# design.net
KiCad netlist of a schematic drawn in Altium Designer
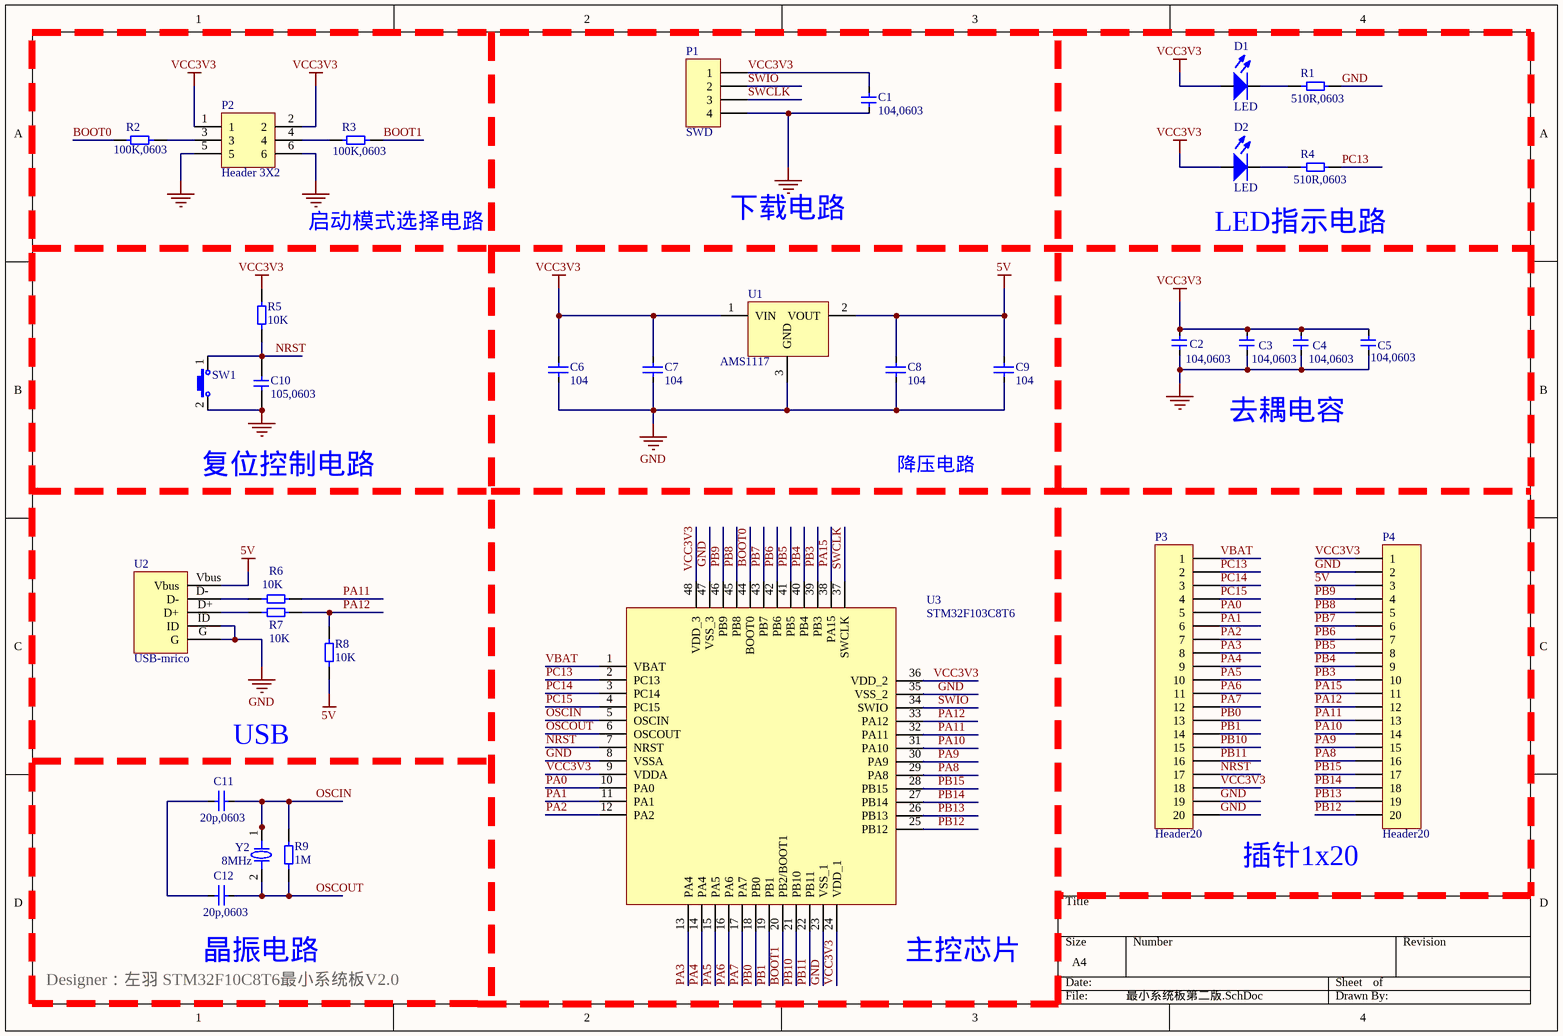
[diagram p0: 最小系统板第二版.SchDoc]

(export (version "E")
  (design (tool "Eeschema 10.0.6"))
  (components
    (comp (ref "C1")
      (value "104,0603")
      (footprint "0603C")
      (description "电容")
      (libsource (lib "原理图库") (part "CAP"))
    )
    (comp (ref "C2")
      (value "104,0603")
      (footprint "0603C")
      (description "电容")
      (libsource (lib "原理图库") (part "CAP"))
    )
    (comp (ref "C3")
      (value "104,0603")
      (footprint "0603C")
      (description "电容")
      (libsource (lib "原理图库") (part "CAP"))
    )
    (comp (ref "C4")
      (value "104,0603")
      (footprint "0603C")
      (description "电容")
      (libsource (lib "原理图库") (part "CAP"))
    )
    (comp (ref "C5")
      (value "104,0603")
      (footprint "0603C")
      (description "电容")
      (libsource (lib "原理图库") (part "CAP"))
    )
    (comp (ref "C6") (value "104") (footprint "0603C") (description "电容") (libsource (lib "") (part "CAP_2")))
    (comp (ref "C7") (value "104") (footprint "0603C") (description "电容") (libsource (lib "") (part "CAP_1")))
    (comp (ref "C8") (value "104") (footprint "0603C") (description "电容") (libsource (lib "") (part "CAP_1")))
    (comp (ref "C9") (value "104") (footprint "0603C") (description "电容") (libsource (lib "") (part "CAP_1")))
    (comp (ref "C10")
      (value "105,0603")
      (footprint "0603C")
      (description "电容")
      (libsource (lib "") (part "CAP_3"))
    )
    (comp (ref "C11")
      (value "20p,0603")
      (footprint "0603C")
      (description "电容")
      (libsource (lib "") (part "CAP_1"))
    )
    (comp (ref "C12")
      (value "20p,0603")
      (footprint "0603C")
      (description "电容")
      (libsource (lib "") (part "CAP_1"))
    )
    (comp (ref "D1")
      (value "LED")
      (footprint "LED-0805B")
      (description "LED灯")
      (libsource (lib "原理图库") (part "LED"))
    )
    (comp (ref "D2")
      (value "LED")
      (footprint "LED-0805B")
      (description "LED灯")
      (libsource (lib "原理图库") (part "LED"))
    )
    (comp (ref "P1") (value "SWD") (footprint "HDR2.54-WI-4P") (libsource (lib "原理图库") (part "SWD")))
    (comp (ref "P2")
      (value "Header 3X2")
      (footprint "Pin HDR2X3/2.54mm-S")
      (libsource (lib "原理图库") (part "Header 3X2"))
    )
    (comp (ref "P3")
      (value "Header20")
      (footprint "Pin HDR1X20/2.54mm-S")
      (libsource (lib "原理图库") (part "Header20"))
    )
    (comp (ref "P4")
      (value "Header20")
      (footprint "Pin HDR1X20/2.54mm-S")
      (libsource (lib "") (part "Header20_1"))
    )
    (comp (ref "R1")
      (value "510R,0603")
      (footprint "0603R")
      (description "电阻")
      (libsource (lib "原理图库") (part "RES"))
    )
    (comp (ref "R2")
      (value "100K,0603")
      (footprint "0603R")
      (description "电阻")
      (libsource (lib "原理图库") (part "RES"))
    )
    (comp (ref "R3")
      (value "100K,0603")
      (footprint "0603R")
      (description "电阻")
      (libsource (lib "原理图库") (part "RES"))
    )
    (comp (ref "R4")
      (value "510R,0603")
      (footprint "0603R")
      (description "电阻")
      (libsource (lib "原理图库") (part "RES"))
    )
    (comp (ref "R5")
      (value "10K")
      (footprint "0603R")
      (description "电阻")
      (libsource (lib "原理图库") (part "RES"))
    )
    (comp (ref "R6")
      (value "10K")
      (footprint "0603R")
      (description "电阻")
      (libsource (lib "原理图库") (part "RES"))
    )
    (comp (ref "R7")
      (value "10K")
      (footprint "0603R")
      (description "电阻")
      (libsource (lib "原理图库") (part "RES"))
    )
    (comp (ref "R8")
      (value "10K")
      (footprint "0603R")
      (description "电阻")
      (libsource (lib "原理图库") (part "RES"))
    )
    (comp (ref "R9")
      (value "1M")
      (footprint "0603R")
      (description "电阻")
      (libsource (lib "原理图库") (part "RES"))
    )
    (comp (ref "SW1")
      (value "KEY")
      (footprint "复位开关")
      (description "按键")
      (libsource (lib "原理图库") (part "RST"))
    )
    (comp (ref "U1")
      (value "AMS1117")
      (footprint "SOT-223_L6.5-W3.5-P2.30-LS7.0-BR")
      (libsource (lib "原理图库") (part "AMS1117 3V3"))
    )
    (comp (ref "U2")
      (value "USB-mrico")
      (footprint "PCBComponent_1 - duplicate")
      (libsource (lib "原理图库") (part "USB-mrico"))
    )
    (comp (ref "U3") (value "STM32F103C8T6") (footprint "LQFP-48_M") (libsource (lib "原理图库") (part "MCU")))
    (comp (ref "Y2")
      (value "8MHz")
      (footprint "直插外部晶振")
      (description "晶振")
      (libsource (lib "原理图库") (part "Crystal oscillator"))
    )
  )
  (nets
    (net (code "2") (name "/BOOT0") (class "Default")
      (node (ref "R2") (pin "1") (pinfunction "1_1") (pintype "passive"))
      (node (ref "U3") (pin "44") (pinfunction "BOOT0_44") (pintype "passive"))
    )
    (net (code "3") (name "/BOOT1") (class "Default")
      (node (ref "R3") (pin "2") (pinfunction "2_2") (pintype "passive"))
      (node (ref "U3") (pin "20") (pinfunction "PB2/BOOT1_20") (pintype "passive"))
    )
    (net (code "4") (name "/NRST") (class "Default")
      (node (ref "C10") (pin "1") (pinfunction "1_1") (pintype "passive"))
      (node (ref "P3") (pin "17") (pinfunction "17_17") (pintype "passive"))
      (node (ref "R5") (pin "2") (pinfunction "2_2") (pintype "passive"))
      (node (ref "SW1") (pin "1") (pinfunction "1_1") (pintype "passive"))
      (node (ref "U3") (pin "7") (pinfunction "NRST_7") (pintype "passive"))
    )
    (net (code "5") (name "/OSCIN") (class "Default")
      (node (ref "C11") (pin "1") (pinfunction "1_1") (pintype "passive"))
      (node (ref "R9") (pin "1") (pinfunction "1_1") (pintype "passive"))
      (node (ref "U3") (pin "5") (pinfunction "OSCIN_5") (pintype "passive"))
      (node (ref "Y2") (pin "1") (pinfunction "1_1") (pintype "passive"))
    )
    (net (code "6") (name "/OSCOUT") (class "Default")
      (node (ref "C12") (pin "1") (pinfunction "1_1") (pintype "passive"))
      (node (ref "R9") (pin "2") (pinfunction "2_2") (pintype "passive"))
      (node (ref "U3") (pin "6") (pinfunction "OSCOUT_6") (pintype "passive"))
      (node (ref "Y2") (pin "2") (pinfunction "2_2") (pintype "passive"))
    )
    (net (code "7") (name "/PA0") (class "Default")
      (node (ref "P3") (pin "5") (pinfunction "5_5") (pintype "passive"))
      (node (ref "U3") (pin "10") (pinfunction "PA0_10") (pintype "passive"))
    )
    (net (code "8") (name "/PA1") (class "Default")
      (node (ref "P3") (pin "6") (pinfunction "6_6") (pintype "passive"))
      (node (ref "U3") (pin "11") (pinfunction "PA1_11") (pintype "passive"))
    )
    (net (code "9") (name "/PA2") (class "Default")
      (node (ref "P3") (pin "7") (pinfunction "7_7") (pintype "passive"))
      (node (ref "U3") (pin "12") (pinfunction "PA2_12") (pintype "passive"))
    )
    (net (code "10") (name "/PA3") (class "Default")
      (node (ref "P3") (pin "8") (pinfunction "8_8") (pintype "passive"))
      (node (ref "U3") (pin "13") (pinfunction "PA4_13") (pintype "passive"))
    )
    (net (code "11") (name "/PA4") (class "Default")
      (node (ref "P3") (pin "9") (pinfunction "9_9") (pintype "passive"))
      (node (ref "U3") (pin "14") (pinfunction "PA4_14") (pintype "passive"))
    )
    (net (code "12") (name "/PA5") (class "Default")
      (node (ref "P3") (pin "10") (pinfunction "10_10") (pintype "passive"))
      (node (ref "U3") (pin "15") (pinfunction "PA5_15") (pintype "passive"))
    )
    (net (code "13") (name "/PA6") (class "Default")
      (node (ref "P3") (pin "11") (pinfunction "11_11") (pintype "passive"))
      (node (ref "U3") (pin "16") (pinfunction "PA6_16") (pintype "passive"))
    )
    (net (code "14") (name "/PA7") (class "Default")
      (node (ref "P3") (pin "12") (pinfunction "12_12") (pintype "passive"))
      (node (ref "U3") (pin "17") (pinfunction "PA7_17") (pintype "passive"))
    )
    (net (code "15") (name "/PA8") (class "Default")
      (node (ref "P4") (pin "16") (pinfunction "16_16") (pintype "passive"))
      (node (ref "U3") (pin "29") (pinfunction "PA8_29") (pintype "passive"))
    )
    (net (code "16") (name "/PA9") (class "Default")
      (node (ref "P4") (pin "15") (pinfunction "15_15") (pintype "passive"))
      (node (ref "U3") (pin "30") (pinfunction "PA9_30") (pintype "passive"))
    )
    (net (code "17") (name "/PA10") (class "Default")
      (node (ref "P4") (pin "14") (pinfunction "14_14") (pintype "passive"))
      (node (ref "U3") (pin "31") (pinfunction "PA10_31") (pintype "passive"))
    )
    (net (code "18") (name "/PA11") (class "Default")
      (node (ref "P4") (pin "13") (pinfunction "13_13") (pintype "passive"))
      (node (ref "R6") (pin "1") (pinfunction "1_1") (pintype "passive"))
      (node (ref "U3") (pin "32") (pinfunction "PA11_32") (pintype "passive"))
    )
    (net (code "19") (name "/PA12") (class "Default")
      (node (ref "P4") (pin "12") (pinfunction "12_12") (pintype "passive"))
      (node (ref "R7") (pin "1") (pinfunction "1_1") (pintype "passive"))
      (node (ref "R8") (pin "1") (pinfunction "1_1") (pintype "passive"))
      (node (ref "U3") (pin "33") (pinfunction "PA12_33") (pintype "passive"))
    )
    (net (code "20") (name "/PA15") (class "Default")
      (node (ref "P4") (pin "11") (pinfunction "11_11") (pintype "passive"))
      (node (ref "U3") (pin "38") (pinfunction "PA15_38") (pintype "passive"))
    )
    (net (code "21") (name "/PB0") (class "Default")
      (node (ref "P3") (pin "13") (pinfunction "13_13") (pintype "passive"))
      (node (ref "U3") (pin "18") (pinfunction "PB0_18") (pintype "passive"))
    )
    (net (code "22") (name "/PB1") (class "Default")
      (node (ref "P3") (pin "14") (pinfunction "14_14") (pintype "passive"))
      (node (ref "U3") (pin "19") (pinfunction "PB1_19") (pintype "passive"))
    )
    (net (code "23") (name "/PB3") (class "Default")
      (node (ref "P4") (pin "10") (pinfunction "10_10") (pintype "passive"))
      (node (ref "U3") (pin "39") (pinfunction "PB3_39") (pintype "passive"))
    )
    (net (code "24") (name "/PB4") (class "Default")
      (node (ref "P4") (pin "9") (pinfunction "9_9") (pintype "passive"))
      (node (ref "U3") (pin "40") (pinfunction "PB4_40") (pintype "passive"))
    )
    (net (code "25") (name "/PB5") (class "Default")
      (node (ref "P4") (pin "8") (pinfunction "8_8") (pintype "passive"))
      (node (ref "U3") (pin "41") (pinfunction "PB5_41") (pintype "passive"))
    )
    (net (code "26") (name "/PB6") (class "Default")
      (node (ref "P4") (pin "7") (pinfunction "7_7") (pintype "passive"))
      (node (ref "U3") (pin "42") (pinfunction "PB6_42") (pintype "passive"))
    )
    (net (code "27") (name "/PB7") (class "Default")
      (node (ref "P4") (pin "6") (pinfunction "6_6") (pintype "passive"))
      (node (ref "U3") (pin "43") (pinfunction "PB7_43") (pintype "passive"))
    )
    (net (code "28") (name "/PB8") (class "Default")
      (node (ref "P4") (pin "5") (pinfunction "5_5") (pintype "passive"))
      (node (ref "U3") (pin "45") (pinfunction "PB8_45") (pintype "passive"))
    )
    (net (code "29") (name "/PB9") (class "Default")
      (node (ref "P4") (pin "4") (pinfunction "4_4") (pintype "passive"))
      (node (ref "U3") (pin "46") (pinfunction "PB9_46") (pintype "passive"))
    )
    (net (code "30") (name "/PB10") (class "Default")
      (node (ref "P3") (pin "15") (pinfunction "15_15") (pintype "passive"))
      (node (ref "U3") (pin "21") (pinfunction "PB10_21") (pintype "passive"))
    )
    (net (code "31") (name "/PB11") (class "Default")
      (node (ref "P3") (pin "16") (pinfunction "16_16") (pintype "passive"))
      (node (ref "U3") (pin "22") (pinfunction "PB11_22") (pintype "passive"))
    )
    (net (code "32") (name "/PB12") (class "Default")
      (node (ref "P4") (pin "20") (pinfunction "20_20") (pintype "passive"))
      (node (ref "U3") (pin "25") (pinfunction "PB12_25") (pintype "passive"))
    )
    (net (code "33") (name "/PB13") (class "Default")
      (node (ref "P4") (pin "19") (pinfunction "19_19") (pintype "passive"))
      (node (ref "U3") (pin "26") (pinfunction "PB13_26") (pintype "passive"))
    )
    (net (code "34") (name "/PB14") (class "Default")
      (node (ref "P4") (pin "18") (pinfunction "18_18") (pintype "passive"))
      (node (ref "U3") (pin "27") (pinfunction "PB14_27") (pintype "passive"))
    )
    (net (code "35") (name "/PB15") (class "Default")
      (node (ref "P4") (pin "17") (pinfunction "17_17") (pintype "passive"))
      (node (ref "U3") (pin "28") (pinfunction "PB15_28") (pintype "passive"))
    )
    (net (code "36") (name "/PC13") (class "Default")
      (node (ref "P3") (pin "2") (pinfunction "2_2") (pintype "passive"))
      (node (ref "R4") (pin "1") (pinfunction "1_1") (pintype "passive"))
      (node (ref "U3") (pin "2") (pinfunction "PC13_2") (pintype "passive"))
    )
    (net (code "37") (name "/PC14") (class "Default")
      (node (ref "P3") (pin "3") (pinfunction "3_3") (pintype "passive"))
      (node (ref "U3") (pin "3") (pinfunction "PC14_3") (pintype "passive"))
    )
    (net (code "38") (name "/PC15") (class "Default")
      (node (ref "P3") (pin "4") (pinfunction "4_4") (pintype "passive"))
      (node (ref "U3") (pin "4") (pinfunction "PC15_4") (pintype "passive"))
    )
    (net (code "39") (name "/SWCLK") (class "Default")
      (node (ref "P1") (pin "3") (pinfunction "3_3") (pintype "passive"))
      (node (ref "U3") (pin "37") (pinfunction "SWCLK_37") (pintype "passive"))
    )
    (net (code "40") (name "/SWIO") (class "Default")
      (node (ref "P1") (pin "2") (pinfunction "2_2") (pintype "passive"))
      (node (ref "U3") (pin "34") (pinfunction "SWIO_34") (pintype "passive"))
    )
    (net (code "41") (name "/VBAT") (class "Default")
      (node (ref "P3") (pin "1") (pinfunction "1_1") (pintype "passive"))
      (node (ref "U3") (pin "1") (pinfunction "VBAT_1") (pintype "passive"))
    )
    (net (code "42") (name "5V") (class "Default")
      (node (ref "C8") (pin "1") (pinfunction "1_1") (pintype "passive"))
      (node (ref "C9") (pin "1") (pinfunction "1_1") (pintype "passive"))
      (node (ref "P4") (pin "3") (pinfunction "3_3") (pintype "passive"))
      (node (ref "R8") (pin "2") (pinfunction "2_2") (pintype "passive"))
      (node (ref "U1") (pin "2") (pinfunction "VOUT_2") (pintype "passive"))
      (node (ref "U2") (pin "1") (pinfunction "Vbus_1") (pintype "passive"))
    )
    (net (code "43") (name "GND") (class "Default")
      (node (ref "C1") (pin "2") (pinfunction "2_2") (pintype "passive"))
      (node (ref "C10") (pin "2") (pinfunction "2_2") (pintype "passive"))
      (node (ref "C2") (pin "2") (pinfunction "2_2") (pintype "passive"))
      (node (ref "C3") (pin "2") (pinfunction "2_2") (pintype "passive"))
      (node (ref "C4") (pin "2") (pinfunction "2_2") (pintype "passive"))
      (node (ref "C5") (pin "2") (pinfunction "2_2") (pintype "passive"))
      (node (ref "C6") (pin "1") (pinfunction "1_1") (pintype "passive"))
      (node (ref "C7") (pin "2") (pinfunction "2_2") (pintype "passive"))
      (node (ref "C8") (pin "2") (pinfunction "2_2") (pintype "passive"))
      (node (ref "C9") (pin "2") (pinfunction "2_2") (pintype "passive"))
      (node (ref "P1") (pin "4") (pinfunction "4_4") (pintype "passive"))
      (node (ref "P2") (pin "5") (pinfunction "5_5") (pintype "passive"))
      (node (ref "P2") (pin "6") (pinfunction "6_6") (pintype "passive"))
      (node (ref "P3") (pin "19") (pinfunction "19_19") (pintype "passive"))
      (node (ref "P3") (pin "20") (pinfunction "20_20") (pintype "passive"))
      (node (ref "P4") (pin "2") (pinfunction "2_2") (pintype "passive"))
      (node (ref "R1") (pin "1") (pinfunction "1_1") (pintype "passive"))
      (node (ref "SW1") (pin "2") (pinfunction "2_2") (pintype "passive"))
      (node (ref "U1") (pin "3") (pinfunction "GND_3") (pintype "passive"))
      (node (ref "U2") (pin "4") (pinfunction "ID_4") (pintype "passive"))
      (node (ref "U2") (pin "5") (pinfunction "G_5") (pintype "passive"))
      (node (ref "U3") (pin "23") (pinfunction "VSS_1_23") (pintype "passive"))
      (node (ref "U3") (pin "35") (pinfunction "VSS_2_35") (pintype "passive"))
      (node (ref "U3") (pin "47") (pinfunction "VSS_3_47") (pintype "passive"))
      (node (ref "U3") (pin "8") (pinfunction "VSSA_8") (pintype "passive"))
    )
    (net (code "44") (name "Net-(C11-Pad2)") (class "Default")
      (node (ref "C11") (pin "2") (pinfunction "2_2") (pintype "passive"))
      (node (ref "C12") (pin "2") (pinfunction "2_2") (pintype "passive"))
    )
    (net (code "45") (name "Net-(D1-PadK)") (class "Default")
      (node (ref "D1") (pin "K") (pinfunction "K_K") (pintype "passive"))
      (node (ref "R1") (pin "2") (pinfunction "2_2") (pintype "passive"))
    )
    (net (code "46") (name "Net-(D2-PadK)") (class "Default")
      (node (ref "D2") (pin "K") (pinfunction "K_K") (pintype "passive"))
      (node (ref "R4") (pin "2") (pinfunction "2_2") (pintype "passive"))
    )
    (net (code "47") (name "Net-(P2-Pad3)") (class "Default")
      (node (ref "P2") (pin "3") (pinfunction "3_3") (pintype "passive"))
      (node (ref "R2") (pin "2") (pinfunction "2_2") (pintype "passive"))
    )
    (net (code "48") (name "Net-(P2-Pad4)") (class "Default")
      (node (ref "P2") (pin "4") (pinfunction "4_4") (pintype "passive"))
      (node (ref "R3") (pin "1") (pinfunction "1_1") (pintype "passive"))
    )
    (net (code "49") (name "Net-(U2-D+)") (class "Default")
      (node (ref "R7") (pin "2") (pinfunction "2_2") (pintype "passive"))
      (node (ref "U2") (pin "3") (pinfunction "D+_3") (pintype "passive"))
    )
    (net (code "50") (name "Net-(U2-D-)") (class "Default")
      (node (ref "R6") (pin "2") (pinfunction "2_2") (pintype "passive"))
      (node (ref "U2") (pin "2") (pinfunction "D-_2") (pintype "passive"))
    )
    (net (code "51") (name "VCC3V3") (class "Default")
      (node (ref "C1") (pin "1") (pinfunction "1_1") (pintype "passive"))
      (node (ref "C2") (pin "1") (pinfunction "1_1") (pintype "passive"))
      (node (ref "C3") (pin "1") (pinfunction "1_1") (pintype "passive"))
      (node (ref "C4") (pin "1") (pinfunction "1_1") (pintype "passive"))
      (node (ref "C5") (pin "1") (pinfunction "1_1") (pintype "passive"))
      (node (ref "C6") (pin "2") (pinfunction "2_2") (pintype "passive"))
      (node (ref "C7") (pin "1") (pinfunction "1_1") (pintype "passive"))
      (node (ref "D1") (pin "A") (pinfunction "A_A") (pintype "passive"))
      (node (ref "D2") (pin "A") (pinfunction "A_A") (pintype "passive"))
      (node (ref "P1") (pin "1") (pinfunction "1_1") (pintype "passive"))
      (node (ref "P2") (pin "1") (pinfunction "1_1") (pintype "passive"))
      (node (ref "P2") (pin "2") (pinfunction "2_2") (pintype "passive"))
      (node (ref "P3") (pin "18") (pinfunction "18_18") (pintype "passive"))
      (node (ref "P4") (pin "1") (pinfunction "1_1") (pintype "passive"))
      (node (ref "R5") (pin "1") (pinfunction "1_1") (pintype "passive"))
      (node (ref "U1") (pin "1") (pinfunction "VIN_1") (pintype "passive"))
      (node (ref "U3") (pin "24") (pinfunction "VDD_1_24") (pintype "passive"))
      (node (ref "U3") (pin "36") (pinfunction "VDD_2_36") (pintype "passive"))
      (node (ref "U3") (pin "48") (pinfunction "VDD_3_48") (pintype "passive"))
      (node (ref "U3") (pin "9") (pinfunction "VDDA_9") (pintype "passive"))
    )
  )
)
